# STM32405RG.net
KiCad netlist of a schematic drawn in Altium Designer
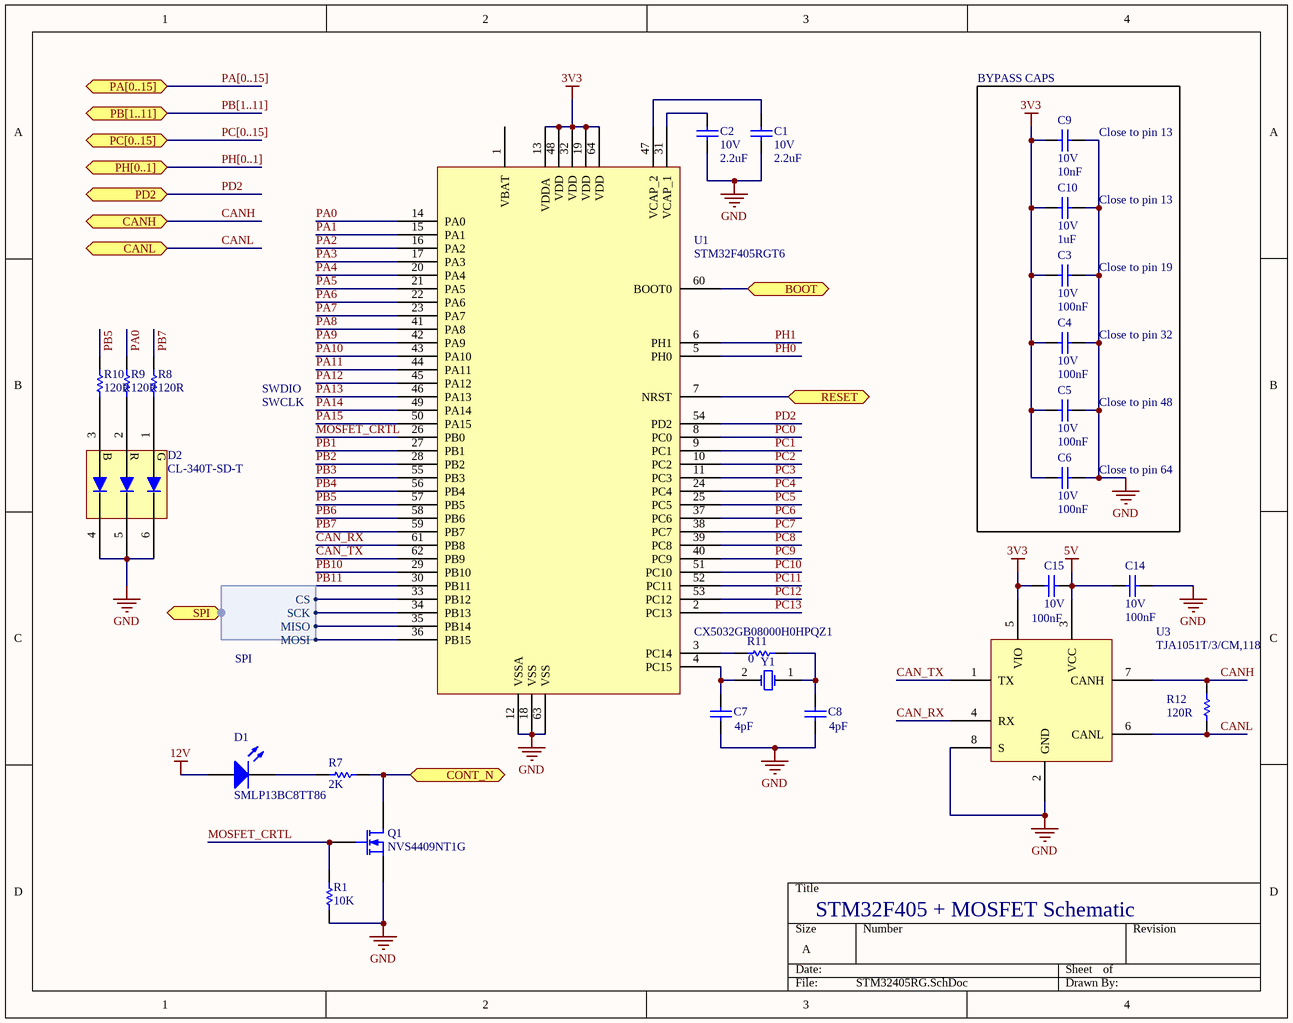
[diagram p0: STM32405RG.SchDoc]

(export (version "E")
  (design (tool "Eeschema 10.0.6"))
  (components
    (comp (ref "C1")
      (value "10V")
      (footprint "C0805")
      (description "C0805C225K8RACAUTO. 2.2µF ±10% 10V Ceramic Capacitor X7R 0805 (2012 Metric)")
      (fields (field (name "ALTIUM_VALUE") "2.2uF") (field (name "PUBLISHER") "Altium Limited"))
      (libsource (lib "Miscellaneous Devices") (part "Cap"))
    )
    (comp (ref "C2")
      (value "10V")
      (footprint "C0805")
      (description "C0805C225K8RACAUTO. 2.2µF ±10% 10V Ceramic Capacitor X7R 0805 (2012 Metric)")
      (fields (field (name "ALTIUM_VALUE") "2.2uF") (field (name "PUBLISHER") "Altium Limited"))
      (libsource (lib "Miscellaneous Devices") (part "Cap"))
    )
    (comp (ref "C3")
      (value "10V")
      (footprint "C0805")
      (description "C0805C104K8RACTU. 0.1µF ±10% 10V Ceramic Capacitor X7R 0805 (2012 Metric)")
      (fields (field (name "ALTIUM_VALUE") "100nF") (field (name "PUBLISHER") "Altium Limited"))
      (libsource (lib "Miscellaneous Devices") (part "Cap"))
    )
    (comp (ref "C4")
      (value "10V")
      (footprint "C0805")
      (description "C0805C104K8RACTU. 0.1µF ±10% 10V Ceramic Capacitor X7R 0805 (2012 Metric)")
      (fields (field (name "ALTIUM_VALUE") "100nF") (field (name "PUBLISHER") "Altium Limited"))
      (libsource (lib "Miscellaneous Devices") (part "Cap"))
    )
    (comp (ref "C5")
      (value "10V")
      (footprint "C0805")
      (description "C0805C104K8RACTU. 0.1µF ±10% 10V Ceramic Capacitor X7R 0805 (2012 Metric)")
      (fields (field (name "ALTIUM_VALUE") "100nF") (field (name "PUBLISHER") "Altium Limited"))
      (libsource (lib "Miscellaneous Devices") (part "Cap"))
    )
    (comp (ref "C6")
      (value "10V")
      (footprint "C0805")
      (description "C0805C104K8RACTU. 0.1µF ±10% 10V Ceramic Capacitor X7R 0805 (2012 Metric)")
      (fields (field (name "ALTIUM_VALUE") "100nF") (field (name "PUBLISHER") "Altium Limited"))
      (libsource (lib "Miscellaneous Devices") (part "Cap"))
    )
    (comp (ref "C7")
      (value "4pF")
      (footprint "C0805")
      (description "CBR08C409B5GAC. 4pF ±0.1pF 50V Ceramic Capacitor C0G, NP0 0805 (2012 Metric)")
      (fields (field (name "Comment") "50V") (field (name "PUBLISHER") "Altium Limited"))
      (libsource (lib "Miscellaneous Devices") (part "Cap"))
    )
    (comp (ref "C8")
      (value "4pF")
      (footprint "C0805")
      (description "CBR08C409B5GAC")
      (fields (field (name "Comment") "50V") (field (name "PUBLISHER") "Altium Limited"))
      (libsource (lib "Miscellaneous Devices") (part "Cap"))
    )
    (comp (ref "C9")
      (value "10V")
      (footprint "C0805")
      (description "C0805C103K8RAC7800. 10000pF ±10% 10V Ceramic Capacitor X7R 0805 (2012 Metric)")
      (fields (field (name "ALTIUM_VALUE") "10nF") (field (name "PUBLISHER") "Altium Limited"))
      (libsource (lib "Miscellaneous Devices") (part "Cap"))
    )
    (comp (ref "C10")
      (value "10V")
      (footprint "C0805")
      (description "CL21B105KPFNNNE. 1µF ±10% 10V Ceramic Capacitor X7R 0805 (2012 Metric)")
      (fields (field (name "ALTIUM_VALUE") "1uF") (field (name "PUBLISHER") "Altium Limited"))
      (libsource (lib "Miscellaneous Devices") (part "Cap"))
    )
    (comp (ref "C14")
      (value "10V")
      (footprint "C0805")
      (description "C0805C104K8RACTU. 0.1µF ±10% 10V Ceramic Capacitor X7R 0805 (2012 Metric)")
      (fields (field (name "ALTIUM_VALUE") "100nF") (field (name "PUBLISHER") "Altium Limited"))
      (libsource (lib "Miscellaneous Devices") (part "Cap"))
    )
    (comp (ref "C15")
      (value "10V")
      (footprint "C0805")
      (description "C0805C104K8RACTU. 0.1µF ±10% 10V Ceramic Capacitor X7R 0805 (2012 Metric)")
      (fields (field (name "ALTIUM_VALUE") "100nF") (field (name "PUBLISHER") "Altium Limited"))
      (libsource (lib "Miscellaneous Devices") (part "Cap"))
    )
    (comp (ref "D1")
      (value "SMLP13BC8TT86")
      (footprint "SMLP13BC8TT86")
      (description "Blue 470nm LED Indication - Discrete 2.9V 2-SMD, No Lead")
      (fields (field (name "PUBLISHER") "Altium Limited"))
      (libsource (lib "Miscellaneous Devices") (part "LED2"))
    )
    (comp (ref "D2")
      (value "CL-340T-SD-T")
      (footprint "CL-340T-SD-T")
      (libsource (lib "MCU") (part "CL-340T-SD-T"))
    )
    (comp (ref "Q1")
      (value "NVS4409NT1G")
      (footprint "NVS4409NT1G")
      (description "N-Channel 25V 700mA (Ta) 280mW (Tj) Surface Mount SC-70-3 (SOT323)")
      (fields (field (name "PUBLISHER") "Altium Limited"))
      (libsource (lib "Miscellaneous Devices") (part "MOSFET-N"))
    )
    (comp (ref "R1")
      (value "10K")
      (footprint "J1-0603")
      (fields (field (name "Comment") "5%") (field (name "PUBLISHER") "Altium Limited"))
      (libsource (lib "Miscellaneous Devices") (part "Res1"))
    )
    (comp (ref "R7")
      (value "2K")
      (footprint "J1-0603")
      (fields (field (name "Comment") "5%") (field (name "PUBLISHER") "Altium Limited"))
      (libsource (lib "Miscellaneous Devices") (part "Res1"))
    )
    (comp (ref "R8")
      (value "120R")
      (footprint "J1-0603")
      (fields (field (name "Comment") "1%") (field (name "PUBLISHER") "Altium Limited"))
      (libsource (lib "Miscellaneous Devices") (part "Res1"))
    )
    (comp (ref "R9")
      (value "120R")
      (footprint "J1-0603")
      (fields (field (name "Comment") "1%") (field (name "PUBLISHER") "Altium Limited"))
      (libsource (lib "Miscellaneous Devices") (part "Res1"))
    )
    (comp (ref "R10")
      (value "120R")
      (footprint "J1-0603")
      (fields (field (name "Comment") "1%") (field (name "PUBLISHER") "Altium Limited"))
      (libsource (lib "Miscellaneous Devices") (part "Res1"))
    )
    (comp (ref "R11")
      (value "0")
      (footprint "J1-0603")
      (fields (field (name "Comment") "0603") (field (name "PUBLISHER") "Altium Limited"))
      (libsource (lib "Miscellaneous Devices") (part "Res1"))
    )
    (comp (ref "R12")
      (value "120R")
      (footprint "J1-0603")
      (fields (field (name "Comment") "1%") (field (name "PUBLISHER") "Altium Limited"))
      (libsource (lib "Miscellaneous Devices") (part "Res1"))
    )
    (comp (ref "U1")
      (value "STM32F405RGT6")
      (footprint "STM32F405RGT6TR")
      (libsource (lib "MCU") (part "STM32F405RGT6TR"))
    )
    (comp (ref "U3") (value "TJA1051T/3/CM,118") (libsource (lib "MCU") (part "TJA1050T/CM,118")))
    (comp (ref "Y1")
      (value "CX5032GB08000H0HPQZ1")
      (footprint "CX5032GB08000H0HPQZ1")
      (description "8MHz ±20ppm Crystal 12pF 300 Ohms 2-SMD, No Lead")
      (fields (field (name "PUBLISHER") "Altium Limited"))
      (libsource (lib "Miscellaneous Devices") (part "XTAL"))
    )
  )
  (nets
    (net (code "6") (name "/BOOT") (class "Default")
      (node (ref "U1") (pin "60") (pinfunction "BOOT0_60") (pintype "passive"))
    )
    (net (code "7") (name "/CANH") (class "Default")
      (node (ref "R12") (pin "2") (pinfunction "2_2") (pintype "passive"))
      (node (ref "U3") (pin "7") (pinfunction "CANH_7") (pintype "passive"))
    )
    (net (code "8") (name "/CANL") (class "Default")
      (node (ref "R12") (pin "1") (pinfunction "1_1") (pintype "passive"))
      (node (ref "U3") (pin "6") (pinfunction "CANL_6") (pintype "passive"))
    )
    (net (code "9") (name "/CAN_RX") (class "Default")
      (node (ref "U1") (pin "61") (pinfunction "PB8_61") (pintype "passive"))
      (node (ref "U3") (pin "4") (pinfunction "RX_4") (pintype "passive"))
    )
    (net (code "10") (name "/CAN_TX") (class "Default")
      (node (ref "U1") (pin "62") (pinfunction "PB9_62") (pintype "passive"))
      (node (ref "U3") (pin "1") (pinfunction "TX_1") (pintype "passive"))
    )
    (net (code "11") (name "/CONT_N") (class "Default")
      (node (ref "Q1") (pin "1") (pinfunction "D_1") (pintype "passive"))
      (node (ref "R7") (pin "1") (pinfunction "1_1") (pintype "passive"))
    )
    (net (code "12") (name "/CS") (class "Default")
      (node (ref "U1") (pin "33") (pinfunction "PB12_33") (pintype "passive"))
    )
    (net (code "13") (name "/MISO") (class "Default")
      (node (ref "U1") (pin "35") (pinfunction "PB14_35") (pintype "passive"))
    )
    (net (code "14") (name "/MOSFET_CRTL") (class "Default")
      (node (ref "Q1") (pin "2") (pinfunction "G_2") (pintype "passive"))
      (node (ref "R1") (pin "2") (pinfunction "2_2") (pintype "passive"))
      (node (ref "U1") (pin "26") (pinfunction "PB0_26") (pintype "passive"))
    )
    (net (code "15") (name "/MOSI") (class "Default")
      (node (ref "U1") (pin "36") (pinfunction "PB15_36") (pintype "passive"))
    )
    (net (code "16") (name "/PA0") (class "Default")
      (node (ref "R9") (pin "2") (pinfunction "2_2") (pintype "passive"))
      (node (ref "U1") (pin "14") (pinfunction "PA0_14") (pintype "passive"))
    )
    (net (code "17") (name "/PA1") (class "Default")
      (node (ref "U1") (pin "15") (pinfunction "PA1_15") (pintype "passive"))
    )
    (net (code "18") (name "/PA2") (class "Default")
      (node (ref "U1") (pin "16") (pinfunction "PA2_16") (pintype "passive"))
    )
    (net (code "19") (name "/PA3") (class "Default")
      (node (ref "U1") (pin "17") (pinfunction "PA3_17") (pintype "passive"))
    )
    (net (code "20") (name "/PA4") (class "Default")
      (node (ref "U1") (pin "20") (pinfunction "PA4_20") (pintype "passive"))
    )
    (net (code "21") (name "/PA5") (class "Default")
      (node (ref "U1") (pin "21") (pinfunction "PA5_21") (pintype "passive"))
    )
    (net (code "22") (name "/PA6") (class "Default")
      (node (ref "U1") (pin "22") (pinfunction "PA6_22") (pintype "passive"))
    )
    (net (code "23") (name "/PA7") (class "Default")
      (node (ref "U1") (pin "23") (pinfunction "PA7_23") (pintype "passive"))
    )
    (net (code "24") (name "/PA8") (class "Default")
      (node (ref "U1") (pin "41") (pinfunction "PA8_41") (pintype "passive"))
    )
    (net (code "25") (name "/PA9") (class "Default")
      (node (ref "U1") (pin "42") (pinfunction "PA9_42") (pintype "passive"))
    )
    (net (code "26") (name "/PA10") (class "Default")
      (node (ref "U1") (pin "43") (pinfunction "PA10_43") (pintype "passive"))
    )
    (net (code "27") (name "/PA11") (class "Default")
      (node (ref "U1") (pin "44") (pinfunction "PA11_44") (pintype "passive"))
    )
    (net (code "28") (name "/PA12") (class "Default")
      (node (ref "U1") (pin "45") (pinfunction "PA12_45") (pintype "passive"))
    )
    (net (code "29") (name "/PA13") (class "Default")
      (node (ref "U1") (pin "46") (pinfunction "PA13_46") (pintype "passive"))
    )
    (net (code "30") (name "/PA14") (class "Default")
      (node (ref "U1") (pin "49") (pinfunction "PA14_49") (pintype "passive"))
    )
    (net (code "31") (name "/PA15") (class "Default")
      (node (ref "U1") (pin "50") (pinfunction "PA15_50") (pintype "passive"))
    )
    (net (code "33") (name "/PB1") (class "Default")
      (node (ref "U1") (pin "27") (pinfunction "PB1_27") (pintype "passive"))
    )
    (net (code "34") (name "/PB2") (class "Default")
      (node (ref "U1") (pin "28") (pinfunction "PB2_28") (pintype "passive"))
    )
    (net (code "35") (name "/PB3") (class "Default")
      (node (ref "U1") (pin "55") (pinfunction "PB3_55") (pintype "passive"))
    )
    (net (code "36") (name "/PB4") (class "Default")
      (node (ref "U1") (pin "56") (pinfunction "PB4_56") (pintype "passive"))
    )
    (net (code "37") (name "/PB5") (class "Default")
      (node (ref "R10") (pin "2") (pinfunction "2_2") (pintype "passive"))
      (node (ref "U1") (pin "57") (pinfunction "PB5_57") (pintype "passive"))
    )
    (net (code "38") (name "/PB6") (class "Default")
      (node (ref "U1") (pin "58") (pinfunction "PB6_58") (pintype "passive"))
    )
    (net (code "39") (name "/PB7") (class "Default")
      (node (ref "R8") (pin "2") (pinfunction "2_2") (pintype "passive"))
      (node (ref "U1") (pin "59") (pinfunction "PB7_59") (pintype "passive"))
    )
    (net (code "40") (name "/PB10") (class "Default")
      (node (ref "U1") (pin "29") (pinfunction "PB10_29") (pintype "passive"))
    )
    (net (code "41") (name "/PB11") (class "Default")
      (node (ref "U1") (pin "30") (pinfunction "PB11_30") (pintype "passive"))
    )
    (net (code "43") (name "/PC0") (class "Default")
      (node (ref "U1") (pin "8") (pinfunction "PC0_8") (pintype "passive"))
    )
    (net (code "44") (name "/PC1") (class "Default")
      (node (ref "U1") (pin "9") (pinfunction "PC1_9") (pintype "passive"))
    )
    (net (code "45") (name "/PC2") (class "Default")
      (node (ref "U1") (pin "10") (pinfunction "PC2_10") (pintype "passive"))
    )
    (net (code "46") (name "/PC3") (class "Default")
      (node (ref "U1") (pin "11") (pinfunction "PC3_11") (pintype "passive"))
    )
    (net (code "47") (name "/PC4") (class "Default")
      (node (ref "U1") (pin "24") (pinfunction "PC4_24") (pintype "passive"))
    )
    (net (code "48") (name "/PC5") (class "Default")
      (node (ref "U1") (pin "25") (pinfunction "PC5_25") (pintype "passive"))
    )
    (net (code "49") (name "/PC6") (class "Default")
      (node (ref "U1") (pin "37") (pinfunction "PC6_37") (pintype "passive"))
    )
    (net (code "50") (name "/PC7") (class "Default")
      (node (ref "U1") (pin "38") (pinfunction "PC7_38") (pintype "passive"))
    )
    (net (code "51") (name "/PC8") (class "Default")
      (node (ref "U1") (pin "39") (pinfunction "PC8_39") (pintype "passive"))
    )
    (net (code "52") (name "/PC9") (class "Default")
      (node (ref "U1") (pin "40") (pinfunction "PC9_40") (pintype "passive"))
    )
    (net (code "53") (name "/PC10") (class "Default")
      (node (ref "U1") (pin "51") (pinfunction "PC10_51") (pintype "passive"))
    )
    (net (code "54") (name "/PC11") (class "Default")
      (node (ref "U1") (pin "52") (pinfunction "PC11_52") (pintype "passive"))
    )
    (net (code "55") (name "/PC12") (class "Default")
      (node (ref "U1") (pin "53") (pinfunction "PC12_53") (pintype "passive"))
    )
    (net (code "56") (name "/PC13") (class "Default")
      (node (ref "U1") (pin "2") (pinfunction "PC13_2") (pintype "passive"))
    )
    (net (code "58") (name "/PD2") (class "Default")
      (node (ref "U1") (pin "54") (pinfunction "PD2_54") (pintype "passive"))
    )
    (net (code "59") (name "/PH0") (class "Default")
      (node (ref "U1") (pin "5") (pinfunction "PH0_5") (pintype "passive"))
    )
    (net (code "60") (name "/PH1") (class "Default")
      (node (ref "U1") (pin "6") (pinfunction "PH1_6") (pintype "passive"))
    )
    (net (code "62") (name "/RESET") (class "Default")
      (node (ref "U1") (pin "7") (pinfunction "NRST_7") (pintype "passive"))
    )
    (net (code "63") (name "/SCK") (class "Default")
      (node (ref "U1") (pin "34") (pinfunction "PB13_34") (pintype "passive"))
    )
    (net (code "65") (name "3V3") (class "Default")
      (node (ref "C10") (pin "2") (pinfunction "2_2") (pintype "passive"))
      (node (ref "C15") (pin "1") (pinfunction "1_1") (pintype "passive"))
      (node (ref "C3") (pin "1") (pinfunction "1_1") (pintype "passive"))
      (node (ref "C4") (pin "1") (pinfunction "1_1") (pintype "passive"))
      (node (ref "C5") (pin "1") (pinfunction "1_1") (pintype "passive"))
      (node (ref "C6") (pin "1") (pinfunction "1_1") (pintype "passive"))
      (node (ref "C9") (pin "1") (pinfunction "1_1") (pintype "passive"))
      (node (ref "U1") (pin "13") (pinfunction "VDDA_13") (pintype "power_in"))
      (node (ref "U1") (pin "19") (pinfunction "VDD_19") (pintype "power_in"))
      (node (ref "U1") (pin "32") (pinfunction "VDD_32") (pintype "power_in"))
      (node (ref "U1") (pin "48") (pinfunction "VDD_48") (pintype "power_in"))
      (node (ref "U1") (pin "64") (pinfunction "VDD_64") (pintype "power_in"))
      (node (ref "U3") (pin "5") (pinfunction "VIO_5") (pintype "power_in"))
    )
    (net (code "66") (name "5V") (class "Default")
      (node (ref "C14") (pin "1") (pinfunction "1_1") (pintype "passive"))
      (node (ref "C15") (pin "2") (pinfunction "2_2") (pintype "passive"))
      (node (ref "U3") (pin "3") (pinfunction "VCC_3") (pintype "power_in"))
    )
    (net (code "67") (name "12V") (class "Default")
      (node (ref "D1") (pin "1") (pinfunction "A_1") (pintype "passive"))
    )
    (net (code "68") (name "GND") (class "Default")
      (node (ref "C1") (pin "1") (pinfunction "1_1") (pintype "passive"))
      (node (ref "C10") (pin "1") (pinfunction "1_1") (pintype "passive"))
      (node (ref "C14") (pin "2") (pinfunction "2_2") (pintype "passive"))
      (node (ref "C2") (pin "1") (pinfunction "1_1") (pintype "passive"))
      (node (ref "C3") (pin "2") (pinfunction "2_2") (pintype "passive"))
      (node (ref "C4") (pin "2") (pinfunction "2_2") (pintype "passive"))
      (node (ref "C5") (pin "2") (pinfunction "2_2") (pintype "passive"))
      (node (ref "C6") (pin "2") (pinfunction "2_2") (pintype "passive"))
      (node (ref "C7") (pin "1") (pinfunction "1_1") (pintype "passive"))
      (node (ref "C8") (pin "1") (pinfunction "1_1") (pintype "passive"))
      (node (ref "C9") (pin "2") (pinfunction "2_2") (pintype "passive"))
      (node (ref "D2") (pin "4") (pintype "passive"))
      (node (ref "D2") (pin "5") (pintype "passive"))
      (node (ref "D2") (pin "6") (pintype "passive"))
      (node (ref "Q1") (pin "3") (pinfunction "S_3") (pintype "passive"))
      (node (ref "R1") (pin "1") (pinfunction "1_1") (pintype "passive"))
      (node (ref "U1") (pin "12") (pinfunction "VSSA_12") (pintype "power_in"))
      (node (ref "U1") (pin "18") (pinfunction "VSS_18") (pintype "power_in"))
      (node (ref "U1") (pin "63") (pinfunction "VSS_63") (pintype "power_in"))
      (node (ref "U3") (pin "2") (pinfunction "GND_2") (pintype "power_in"))
      (node (ref "U3") (pin "8") (pinfunction "S_8") (pintype "passive"))
    )
    (net (code "69") (name "Net-(D1-K)") (class "Default")
      (node (ref "D1") (pin "2") (pinfunction "K_2") (pintype "passive"))
      (node (ref "R7") (pin "2") (pinfunction "2_2") (pintype "passive"))
    )
    (net (code "70") (name "Net-(D2-Pad1)") (class "Default")
      (node (ref "D2") (pin "1") (pintype "passive"))
      (node (ref "R8") (pin "1") (pinfunction "1_1") (pintype "passive"))
    )
    (net (code "71") (name "Net-(D2-Pad2)") (class "Default")
      (node (ref "D2") (pin "2") (pintype "passive"))
      (node (ref "R9") (pin "1") (pinfunction "1_1") (pintype "passive"))
    )
    (net (code "72") (name "Net-(D2-Pad3)") (class "Default")
      (node (ref "D2") (pin "3") (pintype "passive"))
      (node (ref "R10") (pin "1") (pinfunction "1_1") (pintype "passive"))
    )
    (net (code "73") (name "Net-(U1-PC14)") (class "Default")
      (node (ref "R11") (pin "1") (pinfunction "1_1") (pintype "passive"))
      (node (ref "U1") (pin "3") (pinfunction "PC14_3") (pintype "passive"))
    )
    (net (code "74") (name "Net-(U1-PC15)") (class "Default")
      (node (ref "C7") (pin "2") (pinfunction "2_2") (pintype "passive"))
      (node (ref "U1") (pin "4") (pinfunction "PC15_4") (pintype "passive"))
      (node (ref "Y1") (pin "2") (pinfunction "OSC2_2") (pintype "passive"))
    )
    (net (code "75") (name "Net-(U1-VCAP_1)") (class "Default")
      (node (ref "C2") (pin "2") (pinfunction "2_2") (pintype "passive"))
      (node (ref "U1") (pin "31") (pinfunction "VCAP_1_31") (pintype "power_in"))
    )
    (net (code "76") (name "Net-(U1-VCAP_2)") (class "Default")
      (node (ref "C1") (pin "2") (pinfunction "2_2") (pintype "passive"))
      (node (ref "U1") (pin "47") (pinfunction "VCAP_2_47") (pintype "power_in"))
    )
    (net (code "77") (name "Net-(Y1-OSC1)") (class "Default")
      (node (ref "C8") (pin "2") (pinfunction "2_2") (pintype "passive"))
      (node (ref "R11") (pin "2") (pinfunction "2_2") (pintype "passive"))
      (node (ref "Y1") (pin "1") (pinfunction "OSC1_1") (pintype "passive"))
    )
    (net (code "78") (name "unconnected-(U1-VBAT-Pad1)") (class "Default")
      (node (ref "U1") (pin "1") (pinfunction "VBAT_1") (pintype "power_in"))
    )
  )
)
